# lv_io_temp.net
KiCad netlist of a schematic drawn in Altium Designer
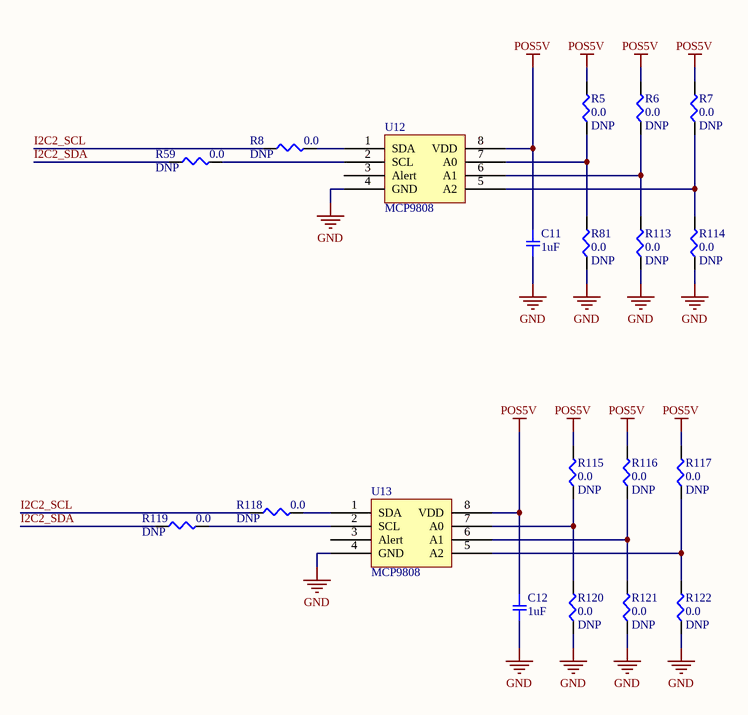
[diagram p0: lv_io_temp.SchDoc]

(export (version "E")
  (design (tool "Eeschema 10.0.6"))
  (components
    (comp (ref "C11")
      (value "1uF")
      (footprint "SMD-0402C")
      (description "C3216X7R2A105K160AM")
      (fields
        (field (name "DIGI-KEY PART NUMBER") "445-6073-1-ND")
        (field (name "PART NUMBER") "https://product.tdk.com/en/search/capacitor/ceramic/mlcc/info?part_no=C3216X7R2A105K160AM")
      )
      (libsource (lib "capacitor") (part "CAP CER 1uF 100V X7R 0402"))
    )
    (comp (ref "C12")
      (value "1uF")
      (footprint "SMD-0402C")
      (description "C3216X7R2A105K160AM")
      (fields
        (field (name "DIGI-KEY PART NUMBER") "445-6073-1-ND")
        (field (name "PART NUMBER") "https://product.tdk.com/en/search/capacitor/ceramic/mlcc/info?part_no=C3216X7R2A105K160AM")
      )
      (libsource (lib "capacitor") (part "CAP CER 1uF 100V X7R 0402"))
    )
    (comp (ref "R5")
      (value "0.0")
      (footprint "SMD-0402-RES")
      (description "RES SMD 0.0OHM JUMPER 1/10W 0402")
      (fields
        (field (name "PART NUMBER") "ERJ-2GE0R00X")
        (field (name "DIGI-KEY PART NUMBER") "P0.0JCT-ND")
        (field (name "DNP") "DNP")
      )
      (libsource (lib "resistor") (part "ERJ-2GE0R00X"))
    )
    (comp (ref "R6")
      (value "0.0")
      (footprint "SMD-0402-RES")
      (description "RES SMD 0.0OHM JUMPER 1/10W 0402")
      (fields
        (field (name "PART NUMBER") "ERJ-2GE0R00X")
        (field (name "DIGI-KEY PART NUMBER") "P0.0JCT-ND")
        (field (name "DNP") "DNP")
      )
      (libsource (lib "resistor") (part "ERJ-2GE0R00X"))
    )
    (comp (ref "R7")
      (value "0.0")
      (footprint "SMD-0402-RES")
      (description "RES SMD 0.0OHM JUMPER 1/10W 0402")
      (fields
        (field (name "PART NUMBER") "ERJ-2GE0R00X")
        (field (name "DIGI-KEY PART NUMBER") "P0.0JCT-ND")
        (field (name "DNP") "DNP")
      )
      (libsource (lib "resistor") (part "ERJ-2GE0R00X"))
    )
    (comp (ref "R8")
      (value "0.0")
      (footprint "SMD-0402-RES")
      (description "RES SMD 0.0OHM JUMPER 1/10W 0402")
      (fields
        (field (name "PART NUMBER") "ERJ-2GE0R00X")
        (field (name "DIGI-KEY PART NUMBER") "P0.0JCT-ND")
        (field (name "DNP") "DNP")
      )
      (libsource (lib "resistor") (part "ERJ-2GE0R00X"))
    )
    (comp (ref "R59")
      (value "0.0")
      (footprint "SMD-0402-RES")
      (description "RES SMD 0.0OHM JUMPER 1/10W 0402")
      (fields
        (field (name "PART NUMBER") "ERJ-2GE0R00X")
        (field (name "DIGI-KEY PART NUMBER") "P0.0JCT-ND")
        (field (name "DNP") "DNP")
      )
      (libsource (lib "resistor") (part "ERJ-2GE0R00X"))
    )
    (comp (ref "R81")
      (value "0.0")
      (footprint "SMD-0402-RES")
      (description "RES SMD 0.0OHM JUMPER 1/10W 0402")
      (fields
        (field (name "PART NUMBER") "ERJ-2GE0R00X")
        (field (name "DIGI-KEY PART NUMBER") "P0.0JCT-ND")
        (field (name "DNP") "DNP")
      )
      (libsource (lib "resistor") (part "ERJ-2GE0R00X"))
    )
    (comp (ref "R113")
      (value "0.0")
      (footprint "SMD-0402-RES")
      (description "RES SMD 0.0OHM JUMPER 1/10W 0402")
      (fields
        (field (name "PART NUMBER") "ERJ-2GE0R00X")
        (field (name "DIGI-KEY PART NUMBER") "P0.0JCT-ND")
        (field (name "DNP") "DNP")
      )
      (libsource (lib "resistor") (part "ERJ-2GE0R00X"))
    )
    (comp (ref "R114")
      (value "0.0")
      (footprint "SMD-0402-RES")
      (description "RES SMD 0.0OHM JUMPER 1/10W 0402")
      (fields
        (field (name "PART NUMBER") "ERJ-2GE0R00X")
        (field (name "DIGI-KEY PART NUMBER") "P0.0JCT-ND")
        (field (name "DNP") "DNP")
      )
      (libsource (lib "resistor") (part "ERJ-2GE0R00X"))
    )
    (comp (ref "R115")
      (value "0.0")
      (footprint "SMD-0402-RES")
      (description "RES SMD 0.0OHM JUMPER 1/10W 0402")
      (fields
        (field (name "PART NUMBER") "ERJ-2GE0R00X")
        (field (name "DIGI-KEY PART NUMBER") "P0.0JCT-ND")
        (field (name "DNP") "DNP")
      )
      (libsource (lib "resistor") (part "ERJ-2GE0R00X"))
    )
    (comp (ref "R116")
      (value "0.0")
      (footprint "SMD-0402-RES")
      (description "RES SMD 0.0OHM JUMPER 1/10W 0402")
      (fields
        (field (name "PART NUMBER") "ERJ-2GE0R00X")
        (field (name "DIGI-KEY PART NUMBER") "P0.0JCT-ND")
        (field (name "DNP") "DNP")
      )
      (libsource (lib "resistor") (part "ERJ-2GE0R00X"))
    )
    (comp (ref "R117")
      (value "0.0")
      (footprint "SMD-0402-RES")
      (description "RES SMD 0.0OHM JUMPER 1/10W 0402")
      (fields
        (field (name "PART NUMBER") "ERJ-2GE0R00X")
        (field (name "DIGI-KEY PART NUMBER") "P0.0JCT-ND")
        (field (name "DNP") "DNP")
      )
      (libsource (lib "resistor") (part "ERJ-2GE0R00X"))
    )
    (comp (ref "R118")
      (value "0.0")
      (footprint "SMD-0402-RES")
      (description "RES SMD 0.0OHM JUMPER 1/10W 0402")
      (fields
        (field (name "PART NUMBER") "ERJ-2GE0R00X")
        (field (name "DIGI-KEY PART NUMBER") "P0.0JCT-ND")
        (field (name "DNP") "DNP")
      )
      (libsource (lib "resistor") (part "ERJ-2GE0R00X"))
    )
    (comp (ref "R119")
      (value "0.0")
      (footprint "SMD-0402-RES")
      (description "RES SMD 0.0OHM JUMPER 1/10W 0402")
      (fields
        (field (name "PART NUMBER") "ERJ-2GE0R00X")
        (field (name "DIGI-KEY PART NUMBER") "P0.0JCT-ND")
        (field (name "DNP") "DNP")
      )
      (libsource (lib "resistor") (part "ERJ-2GE0R00X"))
    )
    (comp (ref "R120")
      (value "0.0")
      (footprint "SMD-0402-RES")
      (description "RES SMD 0.0OHM JUMPER 1/10W 0402")
      (fields
        (field (name "PART NUMBER") "ERJ-2GE0R00X")
        (field (name "DIGI-KEY PART NUMBER") "P0.0JCT-ND")
        (field (name "DNP") "DNP")
      )
      (libsource (lib "resistor") (part "ERJ-2GE0R00X"))
    )
    (comp (ref "R121")
      (value "0.0")
      (footprint "SMD-0402-RES")
      (description "RES SMD 0.0OHM JUMPER 1/10W 0402")
      (fields
        (field (name "PART NUMBER") "ERJ-2GE0R00X")
        (field (name "DIGI-KEY PART NUMBER") "P0.0JCT-ND")
        (field (name "DNP") "DNP")
      )
      (libsource (lib "resistor") (part "ERJ-2GE0R00X"))
    )
    (comp (ref "R122")
      (value "0.0")
      (footprint "SMD-0402-RES")
      (description "RES SMD 0.0OHM JUMPER 1/10W 0402")
      (fields
        (field (name "PART NUMBER") "ERJ-2GE0R00X")
        (field (name "DIGI-KEY PART NUMBER") "P0.0JCT-ND")
        (field (name "DNP") "DNP")
      )
      (libsource (lib "resistor") (part "ERJ-2GE0R00X"))
    )
    (comp (ref "U12")
      (value "MCP9808")
      (footprint "TSOP65P490X65_HS-9N")
      (libsource (lib "temp") (part "MCP9808"))
    )
    (comp (ref "U13")
      (value "MCP9808")
      (footprint "TSOP65P490X65_HS-9N")
      (libsource (lib "temp") (part "MCP9808"))
    )
  )
  (nets
    (net (code "1") (name "/I2C2_SCL") (class "Default")
      (node (ref "R118") (pin "1") (pinfunction "1_1") (pintype "passive"))
      (node (ref "R8") (pin "1") (pinfunction "1_1") (pintype "passive"))
    )
    (net (code "2") (name "/I2C2_SDA") (class "Default")
      (node (ref "R119") (pin "1") (pinfunction "1_1") (pintype "passive"))
      (node (ref "R59") (pin "1") (pinfunction "1_1") (pintype "passive"))
    )
    (net (code "3") (name "GND") (class "Default")
      (node (ref "C11") (pin "2") (pinfunction "2_2") (pintype "passive"))
      (node (ref "C12") (pin "2") (pinfunction "2_2") (pintype "passive"))
      (node (ref "R113") (pin "1") (pinfunction "1_1") (pintype "passive"))
      (node (ref "R114") (pin "1") (pinfunction "1_1") (pintype "passive"))
      (node (ref "R120") (pin "1") (pinfunction "1_1") (pintype "passive"))
      (node (ref "R121") (pin "1") (pinfunction "1_1") (pintype "passive"))
      (node (ref "R122") (pin "1") (pinfunction "1_1") (pintype "passive"))
      (node (ref "R81") (pin "1") (pinfunction "1_1") (pintype "passive"))
      (node (ref "U12") (pin "4") (pinfunction "GND_4") (pintype "passive"))
      (node (ref "U13") (pin "4") (pinfunction "GND_4") (pintype "passive"))
    )
    (net (code "4") (name "Net-(U12-A0)") (class "Default")
      (node (ref "R5") (pin "1") (pinfunction "1_1") (pintype "passive"))
      (node (ref "R81") (pin "2") (pinfunction "2_2") (pintype "passive"))
      (node (ref "U12") (pin "7") (pinfunction "A0_7") (pintype "passive"))
    )
    (net (code "5") (name "Net-(U12-A1)") (class "Default")
      (node (ref "R113") (pin "2") (pinfunction "2_2") (pintype "passive"))
      (node (ref "R6") (pin "1") (pinfunction "1_1") (pintype "passive"))
      (node (ref "U12") (pin "6") (pinfunction "A1_6") (pintype "passive"))
    )
    (net (code "6") (name "Net-(U12-A2)") (class "Default")
      (node (ref "R114") (pin "2") (pinfunction "2_2") (pintype "passive"))
      (node (ref "R7") (pin "1") (pinfunction "1_1") (pintype "passive"))
      (node (ref "U12") (pin "5") (pinfunction "A2_5") (pintype "passive"))
    )
    (net (code "7") (name "Net-(U12-SCL)") (class "Default")
      (node (ref "R59") (pin "2") (pinfunction "2_2") (pintype "passive"))
      (node (ref "U12") (pin "2") (pinfunction "SCL_2") (pintype "passive"))
    )
    (net (code "8") (name "Net-(U12-SDA)") (class "Default")
      (node (ref "R8") (pin "2") (pinfunction "2_2") (pintype "passive"))
      (node (ref "U12") (pin "1") (pinfunction "SDA_1") (pintype "passive"))
    )
    (net (code "9") (name "Net-(U13-A0)") (class "Default")
      (node (ref "R115") (pin "1") (pinfunction "1_1") (pintype "passive"))
      (node (ref "R120") (pin "2") (pinfunction "2_2") (pintype "passive"))
      (node (ref "U13") (pin "7") (pinfunction "A0_7") (pintype "passive"))
    )
    (net (code "10") (name "Net-(U13-A1)") (class "Default")
      (node (ref "R116") (pin "1") (pinfunction "1_1") (pintype "passive"))
      (node (ref "R121") (pin "2") (pinfunction "2_2") (pintype "passive"))
      (node (ref "U13") (pin "6") (pinfunction "A1_6") (pintype "passive"))
    )
    (net (code "11") (name "Net-(U13-A2)") (class "Default")
      (node (ref "R117") (pin "1") (pinfunction "1_1") (pintype "passive"))
      (node (ref "R122") (pin "2") (pinfunction "2_2") (pintype "passive"))
      (node (ref "U13") (pin "5") (pinfunction "A2_5") (pintype "passive"))
    )
    (net (code "12") (name "Net-(U13-SCL)") (class "Default")
      (node (ref "R119") (pin "2") (pinfunction "2_2") (pintype "passive"))
      (node (ref "U13") (pin "2") (pinfunction "SCL_2") (pintype "passive"))
    )
    (net (code "13") (name "Net-(U13-SDA)") (class "Default")
      (node (ref "R118") (pin "2") (pinfunction "2_2") (pintype "passive"))
      (node (ref "U13") (pin "1") (pinfunction "SDA_1") (pintype "passive"))
    )
    (net (code "14") (name "POS5V") (class "Default")
      (node (ref "C11") (pin "1") (pinfunction "1_1") (pintype "passive"))
      (node (ref "C12") (pin "1") (pinfunction "1_1") (pintype "passive"))
      (node (ref "R115") (pin "2") (pinfunction "2_2") (pintype "passive"))
      (node (ref "R116") (pin "2") (pinfunction "2_2") (pintype "passive"))
      (node (ref "R117") (pin "2") (pinfunction "2_2") (pintype "passive"))
      (node (ref "R5") (pin "2") (pinfunction "2_2") (pintype "passive"))
      (node (ref "R6") (pin "2") (pinfunction "2_2") (pintype "passive"))
      (node (ref "R7") (pin "2") (pinfunction "2_2") (pintype "passive"))
      (node (ref "U12") (pin "8") (pinfunction "VDD_8") (pintype "passive"))
      (node (ref "U13") (pin "8") (pinfunction "VDD_8") (pintype "passive"))
    )
    (net (code "15") (name "unconnected-(U12-Alert-Pad3)") (class "Default")
      (node (ref "U12") (pin "3") (pinfunction "Alert_3") (pintype "passive"))
    )
    (net (code "16") (name "unconnected-(U13-Alert-Pad3)") (class "Default")
      (node (ref "U13") (pin "3") (pinfunction "Alert_3") (pintype "passive"))
    )
  )
)
